# THC-schematicRevES.net
KiCad netlist of a schematic drawn in EAGLE
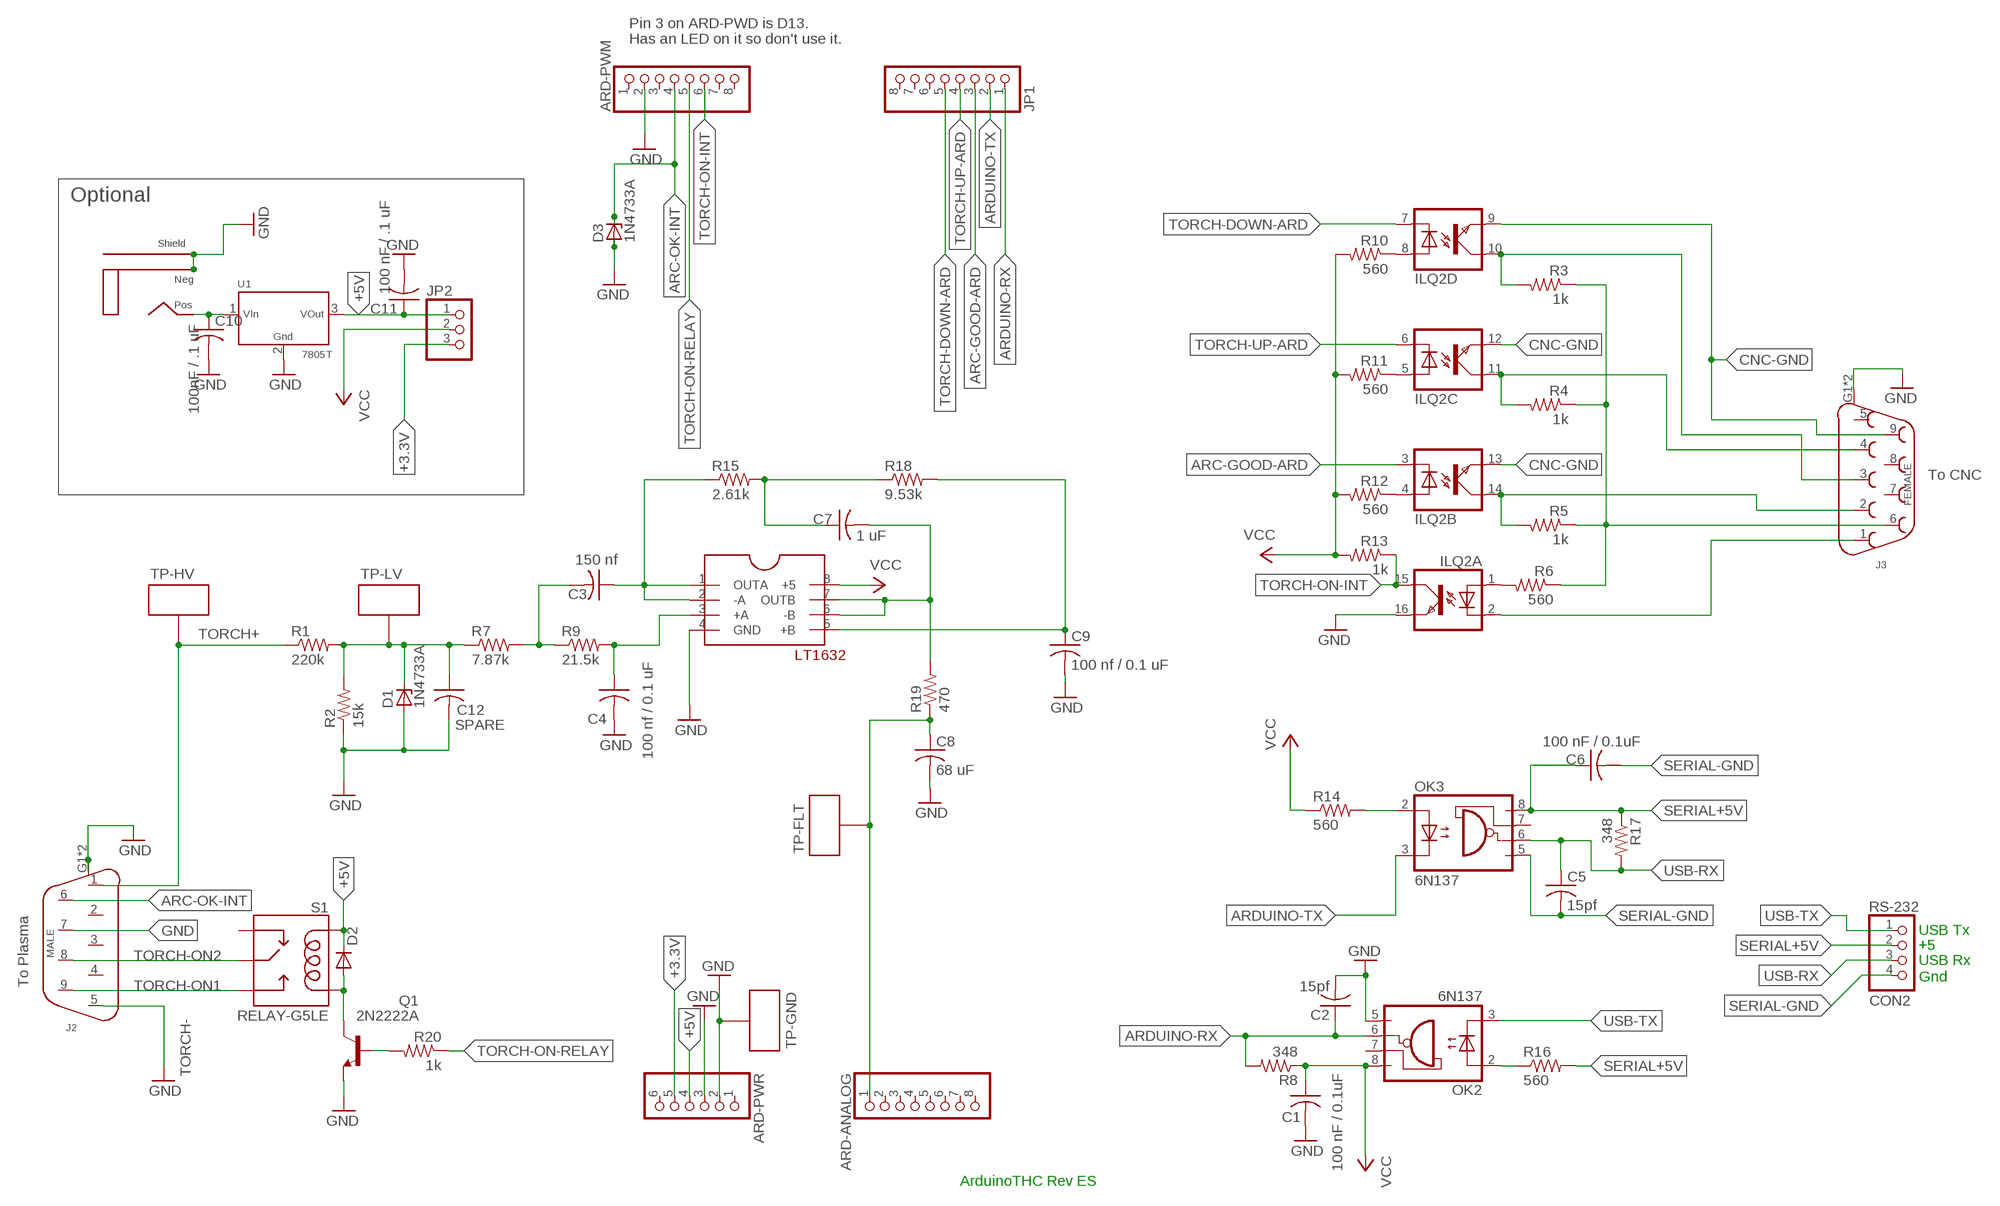
[diagram p0: schematic, sheet 1]

(export (version "E")
  (design (tool "Eeschema 10.0.6"))
  (components
    (comp (ref "ARD-ANALOG")
      (value "PINHD-1X8")
      (footprint "eagle-import:1X08")
      (libsource (lib "eagle-import") (part "PINHD-1X8"))
    )
    (comp (ref "ARD-PWM")
      (value "PINHD-1X8")
      (footprint "eagle-import:1X08")
      (libsource (lib "eagle-import") (part "PINHD-1X8"))
    )
    (comp (ref "ARD-PWR")
      (value "PINHD-1X6")
      (footprint "eagle-import:1X06")
      (libsource (lib "eagle-import") (part "PINHD-1X6"))
    )
    (comp (ref "C1")
      (value "100 nF / 0.1uF")
      (footprint "eagle-import:C025-025X050")
      (libsource (lib "eagle-import") (part "C-US025-025X050"))
    )
    (comp (ref "C2")
      (value "15pf")
      (footprint "eagle-import:C025-025X050")
      (libsource (lib "eagle-import") (part "C-US025-025X050"))
    )
    (comp (ref "C3")
      (value "150 nf")
      (footprint "eagle-import:C025-025X050")
      (libsource (lib "eagle-import") (part "C-US025-025X050"))
    )
    (comp (ref "C4")
      (value "100 nf / 0.1 uF")
      (footprint "eagle-import:C025-025X050")
      (libsource (lib "eagle-import") (part "C-US025-025X050"))
    )
    (comp (ref "C5")
      (value "15pf")
      (footprint "eagle-import:C025-025X050")
      (libsource (lib "eagle-import") (part "C-US025-025X050"))
    )
    (comp (ref "C6")
      (value "100 nF / 0.1uF")
      (footprint "eagle-import:C025-025X050")
      (libsource (lib "eagle-import") (part "C-US025-025X050"))
    )
    (comp (ref "C7")
      (value "1 uF")
      (footprint "eagle-import:C025-025X050")
      (libsource (lib "eagle-import") (part "C-US025-025X050"))
    )
    (comp (ref "C8")
      (value "68 uF")
      (footprint "eagle-import:C025-025X050")
      (libsource (lib "eagle-import") (part "C-US025-025X050"))
    )
    (comp (ref "C9")
      (value "100 nf / 0.1 uF")
      (footprint "eagle-import:C025-025X050")
      (libsource (lib "eagle-import") (part "C-US025-025X050"))
    )
    (comp (ref "C10")
      (value "100nF / .1 uF")
      (footprint "eagle-import:C025-025X050")
      (libsource (lib "eagle-import") (part "C-US025-025X050"))
    )
    (comp (ref "C11")
      (value "100 nF / .1 uF")
      (footprint "eagle-import:C025-025X050")
      (libsource (lib "eagle-import") (part "C-US025-025X050"))
    )
    (comp (ref "C12")
      (value "SPARE")
      (footprint "eagle-import:C025-025X050")
      (libsource (lib "eagle-import") (part "C-US025-025X050"))
    )
    (comp (ref "D1")
      (value "1N4733A")
      (footprint "eagle-import:DO41Z10")
      (libsource (lib "eagle-import") (part "ZPY"))
    )
    (comp (ref "D2")
      (value "1N4001")
      (footprint "eagle-import:DO-204AL")
      (libsource (lib "eagle-import") (part "1N4001"))
    )
    (comp (ref "D3")
      (value "1N4733A")
      (footprint "eagle-import:DO41Z10")
      (libsource (lib "eagle-import") (part "ZPY"))
    )
    (comp (ref "ILQ2")
      (value "ILQ1")
      (footprint "eagle-import:DIL16")
      (fields (field (name "MF") "VISHAY/TELEFUNKEN"))
      (libsource (lib "eagle-import") (part "ILQ1"))
    )
    (comp (ref "J1")
      (value "2.1MM-PLUG-PCB-MNT")
      (footprint "eagle-import:2.1MM-PLUG")
      (libsource (lib "eagle-import") (part "2.1MM-PLUG-PCB-MNT"))
    )
    (comp (ref "J2")
      (value "DB9-MALE")
      (footprint "eagle-import:DB9M-RIGHT-ANGLE")
      (libsource (lib "eagle-import") (part "DB9-MALE"))
    )
    (comp (ref "J3")
      (value "DB9-FEMALE")
      (footprint "eagle-import:DB9F-RIGHT-ANGLE")
      (libsource (lib "eagle-import") (part "DB9-FEMALE"))
    )
    (comp (ref "JP1")
      (value "PINHD-1X8")
      (footprint "eagle-import:1X08")
      (libsource (lib "eagle-import") (part "PINHD-1X8"))
    )
    (comp (ref "JP2")
      (value "PINHD-1X3")
      (footprint "eagle-import:1X03")
      (libsource (lib "eagle-import") (part "PINHD-1X3"))
    )
    (comp (ref "OK2")
      (value "6N137")
      (footprint "eagle-import:DIL08")
      (libsource (lib "eagle-import") (part "6N137"))
    )
    (comp (ref "OK3")
      (value "6N137")
      (footprint "eagle-import:DIL08")
      (libsource (lib "eagle-import") (part "6N137"))
    )
    (comp (ref "Q1")
      (value "2N2222A")
      (footprint "eagle-import:TO18")
      (libsource (lib "eagle-import") (part "2N2222A"))
    )
    (comp (ref "R1")
      (value "220k")
      (footprint "eagle-import:0207_7")
      (libsource (lib "eagle-import") (part "R-US_0207/7"))
    )
    (comp (ref "R2")
      (value "15k")
      (footprint "eagle-import:0207_7")
      (libsource (lib "eagle-import") (part "R-US_0207/7"))
    )
    (comp (ref "R3")
      (value "1k")
      (footprint "eagle-import:0207_7")
      (libsource (lib "eagle-import") (part "R-US_0207/7"))
    )
    (comp (ref "R4")
      (value "1k")
      (footprint "eagle-import:0207_7")
      (libsource (lib "eagle-import") (part "R-US_0207/7"))
    )
    (comp (ref "R5")
      (value "1k")
      (footprint "eagle-import:0207_7")
      (libsource (lib "eagle-import") (part "R-US_0207/7"))
    )
    (comp (ref "R6")
      (value "560")
      (footprint "eagle-import:0207_7")
      (libsource (lib "eagle-import") (part "R-US_0207/7"))
    )
    (comp (ref "R7")
      (value "7.87k")
      (footprint "eagle-import:0207_7")
      (libsource (lib "eagle-import") (part "R-US_0207/7"))
    )
    (comp (ref "R8")
      (value "348")
      (footprint "eagle-import:0207_7")
      (libsource (lib "eagle-import") (part "R-US_0207/7"))
    )
    (comp (ref "R9")
      (value "21.5k")
      (footprint "eagle-import:0207_7")
      (libsource (lib "eagle-import") (part "R-US_0207/7"))
    )
    (comp (ref "R10")
      (value "560")
      (footprint "eagle-import:0207_7")
      (libsource (lib "eagle-import") (part "R-US_0207/7"))
    )
    (comp (ref "R11")
      (value "560")
      (footprint "eagle-import:0207_7")
      (libsource (lib "eagle-import") (part "R-US_0207/7"))
    )
    (comp (ref "R12")
      (value "560")
      (footprint "eagle-import:0207_7")
      (libsource (lib "eagle-import") (part "R-US_0207/7"))
    )
    (comp (ref "R13")
      (value "1k")
      (footprint "eagle-import:0207_7")
      (libsource (lib "eagle-import") (part "R-US_0207/7"))
    )
    (comp (ref "R14")
      (value "560")
      (footprint "eagle-import:0207_7")
      (libsource (lib "eagle-import") (part "R-US_0207/7"))
    )
    (comp (ref "R15")
      (value "2.61k")
      (footprint "eagle-import:0207_7")
      (libsource (lib "eagle-import") (part "R-US_0207/7"))
    )
    (comp (ref "R16")
      (value "560")
      (footprint "eagle-import:0207_7")
      (libsource (lib "eagle-import") (part "R-US_0207/7"))
    )
    (comp (ref "R17")
      (value "348")
      (footprint "eagle-import:0207_7")
      (libsource (lib "eagle-import") (part "R-US_0207/7"))
    )
    (comp (ref "R18")
      (value "9.53k")
      (footprint "eagle-import:0207_7")
      (libsource (lib "eagle-import") (part "R-US_0207/7"))
    )
    (comp (ref "R19")
      (value "470")
      (footprint "eagle-import:0207_7")
      (libsource (lib "eagle-import") (part "R-US_0207/7"))
    )
    (comp (ref "R20")
      (value "1k")
      (footprint "eagle-import:0207_7")
      (libsource (lib "eagle-import") (part "R-US_0207/7"))
    )
    (comp (ref "RS-232")
      (value "CON2")
      (footprint "eagle-import:1X04")
      (libsource (lib "eagle-import") (part "PINHD-1X4"))
    )
    (comp (ref "S1")
      (value "RELAY-G5LE")
      (footprint "eagle-import:RELAY-G5LE")
      (libsource (lib "eagle-import") (part "RELAY-G5LE"))
    )
    (comp (ref "TP-FLT")
      (value "TEST-POINT-.040-HOLE")
      (footprint "eagle-import:TP.040")
      (libsource (lib "eagle-import") (part "TEST-POINT-.040-HOLE"))
    )
    (comp (ref "TP-GND")
      (value "TEST-POINT-.040-HOLE")
      (footprint "eagle-import:TP.040")
      (libsource (lib "eagle-import") (part "TEST-POINT-.040-HOLE"))
    )
    (comp (ref "TP-HV")
      (value "TEST-POINT-.040-HOLE")
      (footprint "eagle-import:TP.040")
      (libsource (lib "eagle-import") (part "TEST-POINT-.040-HOLE"))
    )
    (comp (ref "TP-LV")
      (value "TEST-POINT-.040-HOLE")
      (footprint "eagle-import:TP.040")
      (libsource (lib "eagle-import") (part "TEST-POINT-.040-HOLE"))
    )
    (comp (ref "U$1")
      (value "LT1632")
      (footprint "eagle-import:DIP08")
      (libsource (lib "eagle-import") (part "LT1632"))
    )
    (comp (ref "U1")
      (value "7805T")
      (footprint "eagle-import:TO-220-3")
      (libsource (lib "eagle-import") (part "7805T"))
    )
  )
  (nets
    (net (code "1") (name "+3.3V") (class "Default")
      (node (ref "ARD-PWR") (pin "5") (pinfunction "5_5") (pintype "passive"))
      (node (ref "JP2") (pin "3") (pinfunction "3_3") (pintype "passive"))
    )
    (net (code "2") (name "+5V") (class "Default")
      (node (ref "ARD-PWR") (pin "4") (pinfunction "4_4") (pintype "passive"))
      (node (ref "C11") (pin "1") (pinfunction "1_1") (pintype "passive"))
      (node (ref "D2") (pin "C") (pinfunction "C_C") (pintype "passive"))
      (node (ref "JP2") (pin "1") (pinfunction "1_1") (pintype "passive"))
      (node (ref "S1") (pin "P$5-COIL") (pinfunction "COIL-2_P$5-COIL") (pintype "bidirectional"))
      (node (ref "U1") (pin "3") (pinfunction "VOUT_3") (pintype "bidirectional"))
    )
    (net (code "3") (name "/TORCH-ON1") (class "Default")
      (node (ref "J2") (pin "9") (pinfunction "P$9_9") (pintype "bidirectional"))
      (node (ref "S1") (pin "P$4-NO") (pinfunction "NO_P$4-NO") (pintype "bidirectional"))
    )
    (net (code "4") (name "/TORCH-ON2") (class "Default")
      (node (ref "J2") (pin "8") (pinfunction "P$8_8") (pintype "bidirectional"))
      (node (ref "S1") (pin "P$1-COMMON") (pinfunction "COM_P$1-COMMON") (pintype "bidirectional"))
    )
    (net (code "5") (name "ARC-GOOD-ARD") (class "Default")
      (node (ref "ILQ2") (pin "3") (pinfunction "C_3") (pintype "passive"))
      (node (ref "JP1") (pin "3") (pinfunction "3_3") (pintype "passive"))
    )
    (net (code "6") (name "ARC-OK-INT") (class "Default")
      (node (ref "ARD-PWM") (pin "4") (pinfunction "4_4") (pintype "passive"))
      (node (ref "D3") (pin "C") (pinfunction "C_C") (pintype "passive"))
      (node (ref "J2") (pin "6") (pinfunction "P$6_6") (pintype "bidirectional"))
    )
    (net (code "7") (name "ARDUINO-RX") (class "Default")
      (node (ref "C2") (pin "1") (pinfunction "1_1") (pintype "passive"))
      (node (ref "JP1") (pin "1") (pinfunction "1_1") (pintype "passive"))
      (node (ref "OK2") (pin "6") (pinfunction "VO_6") (pintype "passive"))
      (node (ref "R8") (pin "2") (pinfunction "2_2") (pintype "passive"))
    )
    (net (code "8") (name "ARDUINO-TX") (class "Default")
      (node (ref "JP1") (pin "2") (pinfunction "2_2") (pintype "passive"))
      (node (ref "OK3") (pin "3") (pinfunction "C_3") (pintype "passive"))
    )
    (net (code "9") (name "CNC-GND") (class "Default")
      (node (ref "ILQ2") (pin "12") (pinfunction "EMIT_12") (pintype "passive"))
      (node (ref "ILQ2") (pin "13") (pinfunction "EMIT_13") (pintype "passive"))
      (node (ref "ILQ2") (pin "9") (pinfunction "EMIT_9") (pintype "passive"))
      (node (ref "J3") (pin "9") (pinfunction "P$9_9") (pintype "bidirectional"))
    )
    (net (code "10") (name "GND") (class "Default")
      (node (ref "ARD-PWM") (pin "2") (pinfunction "2_2") (pintype "passive"))
      (node (ref "ARD-PWR") (pin "2") (pinfunction "2_2") (pintype "passive"))
      (node (ref "ARD-PWR") (pin "3") (pinfunction "3_3") (pintype "passive"))
      (node (ref "C1") (pin "2") (pinfunction "2_2") (pintype "passive"))
      (node (ref "C10") (pin "2") (pinfunction "2_2") (pintype "passive"))
      (node (ref "C11") (pin "2") (pinfunction "2_2") (pintype "passive"))
      (node (ref "C12") (pin "2") (pinfunction "2_2") (pintype "passive"))
      (node (ref "C2") (pin "2") (pinfunction "2_2") (pintype "passive"))
      (node (ref "C4") (pin "2") (pinfunction "2_2") (pintype "passive"))
      (node (ref "C8") (pin "2") (pinfunction "2_2") (pintype "passive"))
      (node (ref "C9") (pin "2") (pinfunction "2_2") (pintype "passive"))
      (node (ref "D1") (pin "A") (pinfunction "A_A") (pintype "passive"))
      (node (ref "D3") (pin "A") (pinfunction "A_A") (pintype "passive"))
      (node (ref "ILQ2") (pin "16") (pinfunction "EMIT_16") (pintype "passive"))
      (node (ref "J1") (pin "P$NEG") (pinfunction "P$NEG_P$NEG") (pintype "bidirectional"))
      (node (ref "J1") (pin "P$SHLD") (pinfunction "P$SHLD_P$SHLD") (pintype "bidirectional"))
      (node (ref "J2") (pin "5") (pinfunction "P$5_5") (pintype "bidirectional"))
      (node (ref "J2") (pin "7") (pinfunction "P$7_7") (pintype "bidirectional"))
      (node (ref "J2") (pin "G1") (pinfunction "P$SHLD_G1") (pintype "bidirectional"))
      (node (ref "J2") (pin "G2") (pinfunction "P$SHLD_G2") (pintype "bidirectional"))
      (node (ref "J3") (pin "G1") (pinfunction "P$SHLD_G1") (pintype "bidirectional"))
      (node (ref "J3") (pin "G2") (pinfunction "P$SHLD_G2") (pintype "bidirectional"))
      (node (ref "OK2") (pin "5") (pinfunction "GND_5") (pintype "passive"))
      (node (ref "Q1") (pin "1") (pinfunction "E_1") (pintype "passive"))
      (node (ref "R2") (pin "1") (pinfunction "1_1") (pintype "passive"))
      (node (ref "TP-GND") (pin "P$1") (pinfunction "P$1_P$1") (pintype "bidirectional"))
      (node (ref "U$1") (pin "4") (pinfunction "GND_4") (pintype "bidirectional"))
      (node (ref "U1") (pin "2") (pinfunction "GND_2") (pintype "bidirectional"))
    )
    (net (code "11") (name "Net-(ARD-ANALOG-Pad1)") (class "Default")
      (node (ref "ARD-ANALOG") (pin "1") (pinfunction "1_1") (pintype "passive"))
      (node (ref "C8") (pin "1") (pinfunction "1_1") (pintype "passive"))
      (node (ref "R19") (pin "1") (pinfunction "1_1") (pintype "passive"))
      (node (ref "TP-FLT") (pin "P$1") (pinfunction "P$1_P$1") (pintype "bidirectional"))
    )
    (net (code "12") (name "Net-(C3-Pad2)") (class "Default")
      (node (ref "C3") (pin "2") (pinfunction "2_2") (pintype "passive"))
      (node (ref "R7") (pin "2") (pinfunction "2_2") (pintype "passive"))
      (node (ref "R9") (pin "1") (pinfunction "1_1") (pintype "passive"))
    )
    (net (code "13") (name "Net-(C7-Pad1)") (class "Default")
      (node (ref "C7") (pin "1") (pinfunction "1_1") (pintype "passive"))
      (node (ref "R15") (pin "2") (pinfunction "2_2") (pintype "passive"))
      (node (ref "R18") (pin "1") (pinfunction "1_1") (pintype "passive"))
    )
    (net (code "14") (name "Net-(C12-Pad1)") (class "Default")
      (node (ref "C12") (pin "1") (pinfunction "1_1") (pintype "passive"))
      (node (ref "D1") (pin "C") (pinfunction "C_C") (pintype "passive"))
      (node (ref "R1") (pin "2") (pinfunction "2_2") (pintype "passive"))
      (node (ref "R2") (pin "2") (pinfunction "2_2") (pintype "passive"))
      (node (ref "R7") (pin "1") (pinfunction "1_1") (pintype "passive"))
      (node (ref "TP-LV") (pin "P$1") (pinfunction "P$1_P$1") (pintype "bidirectional"))
    )
    (net (code "15") (name "Net-(ILQ2A-A)") (class "Default")
      (node (ref "ILQ2") (pin "1") (pinfunction "A_1") (pintype "passive"))
      (node (ref "R6") (pin "2") (pinfunction "2_2") (pintype "passive"))
    )
    (net (code "16") (name "Net-(ILQ2A-C)") (class "Default")
      (node (ref "ILQ2") (pin "2") (pinfunction "C_2") (pintype "passive"))
      (node (ref "J3") (pin "1") (pinfunction "P$1_1") (pintype "bidirectional"))
    )
    (net (code "17") (name "Net-(ILQ2B-A)") (class "Default")
      (node (ref "ILQ2") (pin "4") (pinfunction "A_4") (pintype "passive"))
      (node (ref "R12") (pin "1") (pinfunction "1_1") (pintype "passive"))
    )
    (net (code "18") (name "Net-(ILQ2B-COL)") (class "Default")
      (node (ref "ILQ2") (pin "14") (pinfunction "COL_14") (pintype "passive"))
      (node (ref "J3") (pin "2") (pinfunction "P$2_2") (pintype "bidirectional"))
      (node (ref "R5") (pin "2") (pinfunction "2_2") (pintype "passive"))
    )
    (net (code "19") (name "Net-(ILQ2C-A)") (class "Default")
      (node (ref "ILQ2") (pin "5") (pinfunction "A_5") (pintype "passive"))
      (node (ref "R11") (pin "1") (pinfunction "1_1") (pintype "passive"))
    )
    (net (code "20") (name "Net-(ILQ2C-COL)") (class "Default")
      (node (ref "ILQ2") (pin "11") (pinfunction "COL_11") (pintype "passive"))
      (node (ref "J3") (pin "4") (pinfunction "P$4_4") (pintype "bidirectional"))
      (node (ref "R4") (pin "2") (pinfunction "2_2") (pintype "passive"))
    )
    (net (code "21") (name "Net-(ILQ2D-A)") (class "Default")
      (node (ref "ILQ2") (pin "8") (pinfunction "A_8") (pintype "passive"))
      (node (ref "R10") (pin "1") (pinfunction "1_1") (pintype "passive"))
    )
    (net (code "22") (name "Net-(ILQ2D-COL)") (class "Default")
      (node (ref "ILQ2") (pin "10") (pinfunction "COL_10") (pintype "passive"))
      (node (ref "J3") (pin "3") (pinfunction "P$3_3") (pintype "bidirectional"))
      (node (ref "R3") (pin "2") (pinfunction "2_2") (pintype "passive"))
    )
    (net (code "23") (name "Net-(J2-P$1)") (class "Default")
      (node (ref "J2") (pin "1") (pinfunction "P$1_1") (pintype "bidirectional"))
      (node (ref "R1") (pin "1") (pinfunction "1_1") (pintype "passive"))
      (node (ref "TP-HV") (pin "P$1") (pinfunction "P$1_P$1") (pintype "bidirectional"))
    )
    (net (code "24") (name "Net-(J3-P$6)") (class "Default")
      (node (ref "J3") (pin "6") (pinfunction "P$6_6") (pintype "bidirectional"))
      (node (ref "R3") (pin "1") (pinfunction "1_1") (pintype "passive"))
      (node (ref "R4") (pin "1") (pinfunction "1_1") (pintype "passive"))
      (node (ref "R5") (pin "1") (pinfunction "1_1") (pintype "passive"))
      (node (ref "R6") (pin "1") (pinfunction "1_1") (pintype "passive"))
    )
    (net (code "25") (name "Net-(OK2-A)") (class "Default")
      (node (ref "OK2") (pin "2") (pinfunction "A_2") (pintype "passive"))
      (node (ref "R16") (pin "1") (pinfunction "1_1") (pintype "passive"))
    )
    (net (code "26") (name "Net-(OK3-A)") (class "Default")
      (node (ref "OK3") (pin "2") (pinfunction "A_2") (pintype "passive"))
      (node (ref "R14") (pin "2") (pinfunction "2_2") (pintype "passive"))
    )
    (net (code "27") (name "Net-(Q1-B)") (class "Default")
      (node (ref "Q1") (pin "2") (pinfunction "B_2") (pintype "passive"))
      (node (ref "R20") (pin "2") (pinfunction "2_2") (pintype "passive"))
    )
    (net (code "28") (name "Net-(Q1-C)") (class "Default")
      (node (ref "D2") (pin "A") (pinfunction "A_A") (pintype "passive"))
      (node (ref "Q1") (pin "3") (pinfunction "C_3") (pintype "passive"))
      (node (ref "S1") (pin "P$2-COIL") (pinfunction "COIL-1_P$2-COIL") (pintype "bidirectional"))
    )
    (net (code "29") (name "Net-(U$1-+A)") (class "Default")
      (node (ref "C4") (pin "1") (pinfunction "1_1") (pintype "passive"))
      (node (ref "R9") (pin "2") (pinfunction "2_2") (pintype "passive"))
      (node (ref "U$1") (pin "3") (pinfunction "+A_3") (pintype "bidirectional"))
    )
    (net (code "30") (name "Net-(U$1-+B)") (class "Default")
      (node (ref "C9") (pin "1") (pinfunction "1_1") (pintype "passive"))
      (node (ref "R18") (pin "2") (pinfunction "2_2") (pintype "passive"))
      (node (ref "U$1") (pin "5") (pinfunction "+B_5") (pintype "bidirectional"))
    )
    (net (code "31") (name "Net-(U$1--A)") (class "Default")
      (node (ref "C3") (pin "1") (pinfunction "1_1") (pintype "passive"))
      (node (ref "R15") (pin "1") (pinfunction "1_1") (pintype "passive"))
      (node (ref "U$1") (pin "1") (pinfunction "OUTA_1") (pintype "bidirectional"))
      (node (ref "U$1") (pin "2") (pinfunction "-A_2") (pintype "bidirectional"))
    )
    (net (code "32") (name "Net-(U$1--B)") (class "Default")
      (node (ref "C7") (pin "2") (pinfunction "2_2") (pintype "passive"))
      (node (ref "R19") (pin "2") (pinfunction "2_2") (pintype "passive"))
      (node (ref "U$1") (pin "6") (pinfunction "-B_6") (pintype "bidirectional"))
      (node (ref "U$1") (pin "7") (pinfunction "OUTB_7") (pintype "bidirectional"))
    )
    (net (code "33") (name "Net-(U1-VIN)") (class "Default")
      (node (ref "C10") (pin "1") (pinfunction "1_1") (pintype "passive"))
      (node (ref "J1") (pin "P$POS") (pinfunction "P$POS_P$POS") (pintype "bidirectional"))
      (node (ref "U1") (pin "1") (pinfunction "VIN_1") (pintype "bidirectional"))
    )
    (net (code "34") (name "SERIAL+5V") (class "Default")
      (node (ref "C6") (pin "1") (pinfunction "1_1") (pintype "passive"))
      (node (ref "OK3") (pin "8") (pinfunction "VCC_8") (pintype "passive"))
      (node (ref "R16") (pin "2") (pinfunction "2_2") (pintype "passive"))
      (node (ref "R17") (pin "1") (pinfunction "1_1") (pintype "passive"))
      (node (ref "RS-232") (pin "2") (pinfunction "2_2") (pintype "passive"))
    )
    (net (code "35") (name "SERIAL-GND") (class "Default")
      (node (ref "C5") (pin "2") (pinfunction "2_2") (pintype "passive"))
      (node (ref "C6") (pin "2") (pinfunction "2_2") (pintype "passive"))
      (node (ref "OK3") (pin "5") (pinfunction "GND_5") (pintype "passive"))
      (node (ref "RS-232") (pin "4") (pinfunction "4_4") (pintype "passive"))
    )
    (net (code "36") (name "TORCH-DOWN-ARD") (class "Default")
      (node (ref "ILQ2") (pin "7") (pinfunction "C_7") (pintype "passive"))
      (node (ref "JP1") (pin "5") (pinfunction "5_5") (pintype "passive"))
    )
    (net (code "37") (name "TORCH-ON-INT") (class "Default")
      (node (ref "ARD-PWM") (pin "6") (pinfunction "6_6") (pintype "passive"))
      (node (ref "ILQ2") (pin "15") (pinfunction "COL_15") (pintype "passive"))
      (node (ref "R13") (pin "1") (pinfunction "1_1") (pintype "passive"))
    )
    (net (code "38") (name "TORCH-ON-RELAY") (class "Default")
      (node (ref "ARD-PWM") (pin "5") (pinfunction "5_5") (pintype "passive"))
      (node (ref "R20") (pin "1") (pinfunction "1_1") (pintype "passive"))
    )
    (net (code "39") (name "TORCH-UP-ARD") (class "Default")
      (node (ref "ILQ2") (pin "6") (pinfunction "C_6") (pintype "passive"))
      (node (ref "JP1") (pin "4") (pinfunction "4_4") (pintype "passive"))
    )
    (net (code "40") (name "USB-RX") (class "Default")
      (node (ref "C5") (pin "1") (pinfunction "1_1") (pintype "passive"))
      (node (ref "OK3") (pin "6") (pinfunction "VO_6") (pintype "passive"))
      (node (ref "R17") (pin "2") (pinfunction "2_2") (pintype "passive"))
      (node (ref "RS-232") (pin "3") (pinfunction "3_3") (pintype "passive"))
    )
    (net (code "41") (name "USB-TX") (class "Default")
      (node (ref "OK2") (pin "3") (pinfunction "C_3") (pintype "passive"))
      (node (ref "RS-232") (pin "1") (pinfunction "1_1") (pintype "passive"))
    )
    (net (code "42") (name "VCC") (class "Default")
      (node (ref "C1") (pin "1") (pinfunction "1_1") (pintype "passive"))
      (node (ref "JP2") (pin "2") (pinfunction "2_2") (pintype "passive"))
      (node (ref "OK2") (pin "8") (pinfunction "VCC_8") (pintype "passive"))
      (node (ref "R10") (pin "2") (pinfunction "2_2") (pintype "passive"))
      (node (ref "R11") (pin "2") (pinfunction "2_2") (pintype "passive"))
      (node (ref "R12") (pin "2") (pinfunction "2_2") (pintype "passive"))
      (node (ref "R13") (pin "2") (pinfunction "2_2") (pintype "passive"))
      (node (ref "R14") (pin "1") (pinfunction "1_1") (pintype "passive"))
      (node (ref "R8") (pin "1") (pinfunction "1_1") (pintype "passive"))
      (node (ref "U$1") (pin "8") (pinfunction "+5_8") (pintype "bidirectional"))
    )
    (net (code "43") (name "unconnected-(ARD-ANALOG-Pad2)") (class "Default")
      (node (ref "ARD-ANALOG") (pin "2") (pinfunction "2_2") (pintype "passive"))
    )
    (net (code "44") (name "unconnected-(ARD-ANALOG-Pad3)") (class "Default")
      (node (ref "ARD-ANALOG") (pin "3") (pinfunction "3_3") (pintype "passive"))
    )
    (net (code "45") (name "unconnected-(ARD-ANALOG-Pad4)") (class "Default")
      (node (ref "ARD-ANALOG") (pin "4") (pinfunction "4_4") (pintype "passive"))
    )
    (net (code "46") (name "unconnected-(ARD-ANALOG-Pad5)") (class "Default")
      (node (ref "ARD-ANALOG") (pin "5") (pinfunction "5_5") (pintype "passive"))
    )
    (net (code "47") (name "unconnected-(ARD-ANALOG-Pad6)") (class "Default")
      (node (ref "ARD-ANALOG") (pin "6") (pinfunction "6_6") (pintype "passive"))
    )
    (net (code "48") (name "unconnected-(ARD-ANALOG-Pad7)") (class "Default")
      (node (ref "ARD-ANALOG") (pin "7") (pinfunction "7_7") (pintype "passive"))
    )
    (net (code "49") (name "unconnected-(ARD-ANALOG-Pad8)") (class "Default")
      (node (ref "ARD-ANALOG") (pin "8") (pinfunction "8_8") (pintype "passive"))
    )
    (net (code "50") (name "unconnected-(ARD-PWM-Pad1)") (class "Default")
      (node (ref "ARD-PWM") (pin "1") (pinfunction "1_1") (pintype "passive"))
    )
    (net (code "51") (name "unconnected-(ARD-PWM-Pad3)") (class "Default")
      (node (ref "ARD-PWM") (pin "3") (pinfunction "3_3") (pintype "passive"))
    )
    (net (code "52") (name "unconnected-(ARD-PWM-Pad7)") (class "Default")
      (node (ref "ARD-PWM") (pin "7") (pinfunction "7_7") (pintype "passive"))
    )
    (net (code "53") (name "unconnected-(ARD-PWM-Pad8)") (class "Default")
      (node (ref "ARD-PWM") (pin "8") (pinfunction "8_8") (pintype "passive"))
    )
    (net (code "54") (name "unconnected-(ARD-PWR-Pad1)") (class "Default")
      (node (ref "ARD-PWR") (pin "1") (pinfunction "1_1") (pintype "passive"))
    )
    (net (code "55") (name "unconnected-(ARD-PWR-Pad6)") (class "Default")
      (node (ref "ARD-PWR") (pin "6") (pinfunction "6_6") (pintype "passive"))
    )
    (net (code "56") (name "unconnected-(J2-P$2-Pad2)") (class "Default")
      (node (ref "J2") (pin "2") (pinfunction "P$2_2") (pintype "bidirectional"))
    )
    (net (code "57") (name "unconnected-(J2-P$3-Pad3)") (class "Default")
      (node (ref "J2") (pin "3") (pinfunction "P$3_3") (pintype "bidirectional"))
    )
    (net (code "58") (name "unconnected-(J2-P$4-Pad4)") (class "Default")
      (node (ref "J2") (pin "4") (pinfunction "P$4_4") (pintype "bidirectional"))
    )
    (net (code "59") (name "unconnected-(J3-P$5-Pad5)") (class "Default")
      (node (ref "J3") (pin "5") (pinfunction "P$5_5") (pintype "bidirectional"))
    )
    (net (code "60") (name "unconnected-(J3-P$7-Pad7)") (class "Default")
      (node (ref "J3") (pin "7") (pinfunction "P$7_7") (pintype "bidirectional"))
    )
    (net (code "61") (name "unconnected-(J3-P$8-Pad8)") (class "Default")
      (node (ref "J3") (pin "8") (pinfunction "P$8_8") (pintype "bidirectional"))
    )
    (net (code "62") (name "unconnected-(JP1-Pad6)") (class "Default")
      (node (ref "JP1") (pin "6") (pinfunction "6_6") (pintype "passive"))
    )
    (net (code "63") (name "unconnected-(JP1-Pad7)") (class "Default")
      (node (ref "JP1") (pin "7") (pinfunction "7_7") (pintype "passive"))
    )
    (net (code "64") (name "unconnected-(JP1-Pad8)") (class "Default")
      (node (ref "JP1") (pin "8") (pinfunction "8_8") (pintype "passive"))
    )
    (net (code "65") (name "unconnected-(OK2-VE-Pad7)") (class "Default")
      (node (ref "OK2") (pin "7") (pinfunction "VE_7") (pintype "passive"))
    )
    (net (code "66") (name "unconnected-(OK3-VE-Pad7)") (class "Default")
      (node (ref "OK3") (pin "7") (pinfunction "VE_7") (pintype "passive"))
    )
    (net (code "67") (name "unconnected-(S1-NC-PadP$3-NC)") (class "Default")
      (node (ref "S1") (pin "P$3-NC") (pinfunction "NC_P$3-NC") (pintype "bidirectional"))
    )
  )
)
